# pH_Sensor_Unit.net
KiCad netlist of a schematic drawn in Altium Designer
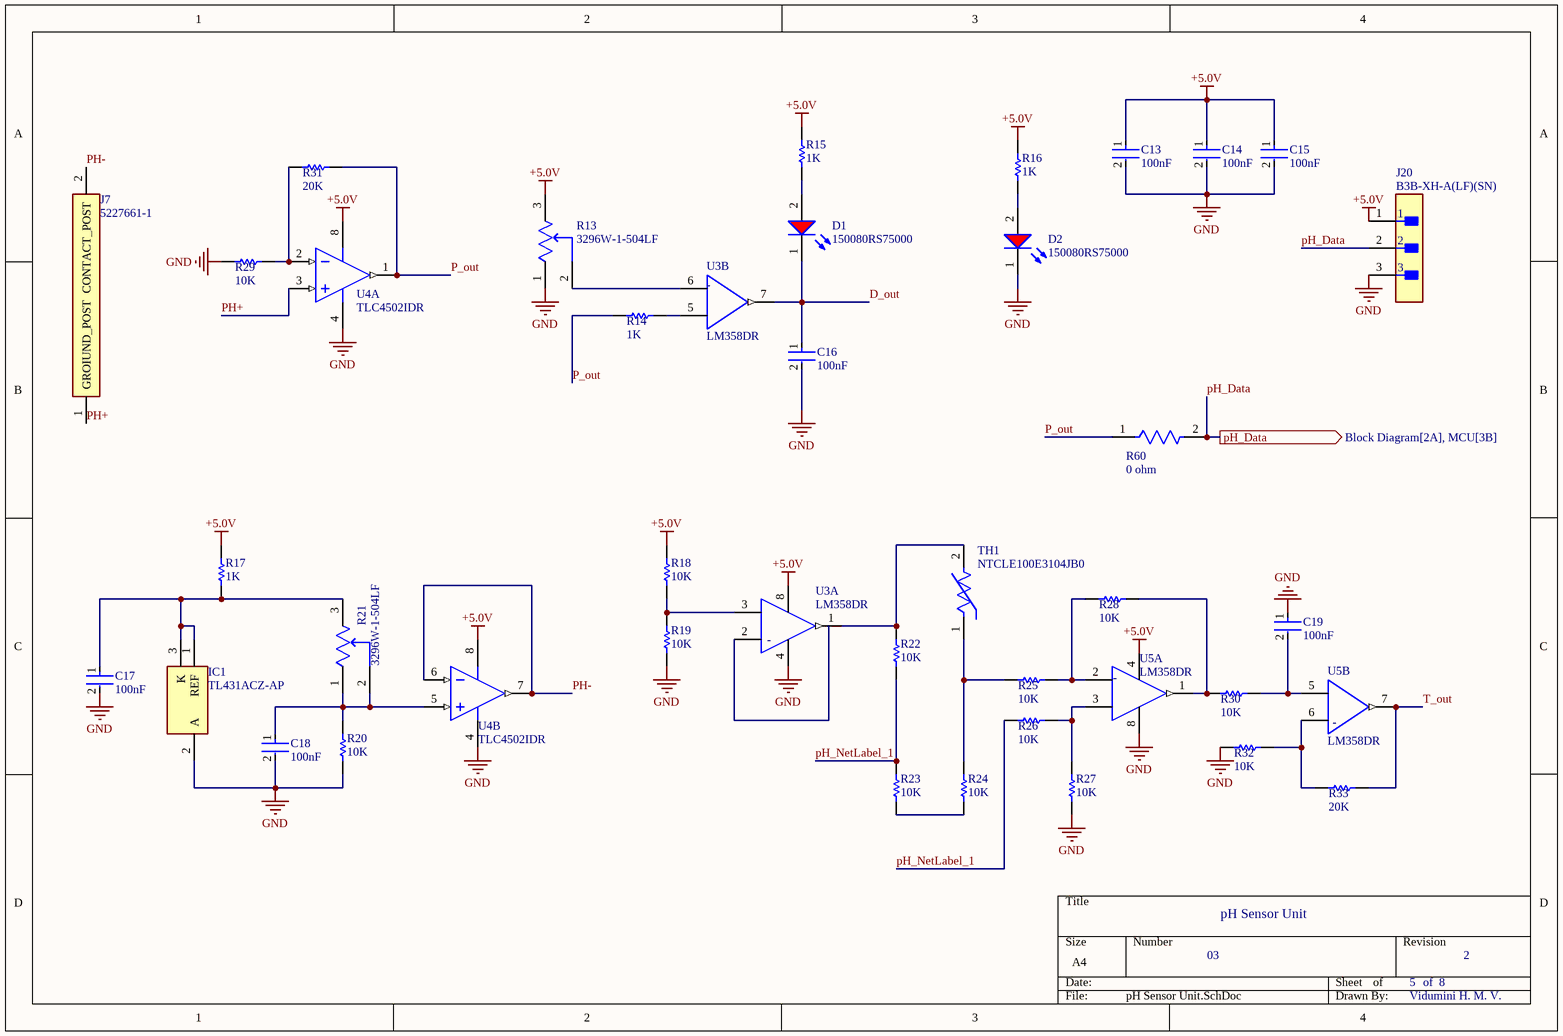
[diagram p0: pH Sensor Unit.SchDoc]

(export (version "E")
  (design (tool "Eeschema 10.0.6"))
  (components
    (comp (ref "C13")
      (value "100nF")
      (footprint "FP-1206-L_3_2_0_2-W_1_6_0-IPC_C")
      (description "General Purpose Ceramic Capacitor, 1206, 100nF, 5%, X7R, 15%, 100V")
      (fields (field (name "TOLERANCE") "5%") (field (name "VOLTAGE") "100V"))
      (libsource (lib "Altium Content Vault") (part "b4654b650e69147ec39a6b967a45e02"))
    )
    (comp (ref "C14")
      (value "100nF")
      (footprint "FP-1206-L_3_2_0_2-W_1_6_0-IPC_C")
      (description "General Purpose Ceramic Capacitor, 1206, 100nF, 5%, X7R, 15%, 100V")
      (fields (field (name "TOLERANCE") "5%") (field (name "VOLTAGE") "100V"))
      (libsource (lib "Altium Content Vault") (part "b4654b650e69147ec39a6b967a45e02"))
    )
    (comp (ref "C15")
      (value "100nF")
      (footprint "FP-1206-L_3_2_0_2-W_1_6_0-IPC_C")
      (description "General Purpose Ceramic Capacitor, 1206, 100nF, 5%, X7R, 15%, 100V")
      (fields (field (name "TOLERANCE") "5%") (field (name "VOLTAGE") "100V"))
      (libsource (lib "Altium Content Vault") (part "b4654b650e69147ec39a6b967a45e02"))
    )
    (comp (ref "C16")
      (value "100nF")
      (footprint "FP-1206-L_3_2_0_2-W_1_6_0-IPC_C")
      (description "General Purpose Ceramic Capacitor, 1206, 100nF, 5%, X7R, 15%, 100V")
      (fields (field (name "TOLERANCE") "5%") (field (name "VOLTAGE") "100V"))
      (libsource (lib "Altium Content Vault") (part "b4654b650e69147ec39a6b967a45e02"))
    )
    (comp (ref "C17")
      (value "100nF")
      (footprint "FP-1206-L_3_2_0_2-W_1_6_0-IPC_C")
      (description "General Purpose Ceramic Capacitor, 1206, 100nF, 5%, X7R, 15%, 100V")
      (fields (field (name "TOLERANCE") "5%") (field (name "VOLTAGE") "100V"))
      (libsource (lib "Altium Content Vault") (part "b4654b650e69147ec39a6b967a45e02"))
    )
    (comp (ref "C18")
      (value "100nF")
      (footprint "FP-1206-L_3_2_0_2-W_1_6_0-IPC_C")
      (description "General Purpose Ceramic Capacitor, 1206, 100nF, 5%, X7R, 15%, 100V")
      (fields (field (name "TOLERANCE") "5%") (field (name "VOLTAGE") "100V"))
      (libsource (lib "Altium Content Vault") (part "b4654b650e69147ec39a6b967a45e02"))
    )
    (comp (ref "C19")
      (value "100nF")
      (footprint "FP-1206-L_3_2_0_2-W_1_6_0-IPC_C")
      (description "General Purpose Ceramic Capacitor, 1206, 100nF, 5%, X7R, 15%, 100V")
      (fields (field (name "TOLERANCE") "5%") (field (name "VOLTAGE") "100V"))
      (libsource (lib "Altium Content Vault") (part "b4654b650e69147ec39a6b967a45e02"))
    )
    (comp (ref "D1")
      (value "150080RS75000")
      (footprint "WL-SMCW_0805_150080xx75000")
      (libsource (lib "Altium Content Vault") (part "LED_Red_2A-1K"))
    )
    (comp (ref "D2")
      (value "150080RS75000")
      (footprint "WL-SMCW_0805_150080xx75000")
      (libsource (lib "Altium Content Vault") (part "LED_Red_2A-1K"))
    )
    (comp (ref "IC1")
      (value "TL431ACZ-AP")
      (footprint "SamacSys:TO-92_BULK")
      (description "Integrated Circuit")
      (fields (field (name "MOUSER PART NUMBER") "511-TL431ACZ-AP"))
      (libsource (lib "*") (part "TL431ACZ-AP"))
    )
    (comp (ref "J7")
      (value "5227661-1")
      (footprint "SamacSys:5227161-1")
      (description "Connector")
      (fields (field (name "MOUSER PART NUMBER") "571-5227661-1"))
      (libsource (lib "*") (part "5227661-1"))
    )
    (comp (ref "J20")
      (value "B3B-XH-A(LF)(SN)")
      (footprint "FP-B3B-XH-A_LF_SN-MFG")
      (description "CONN HEADER VERT 3POS 2.5MM")
      (libsource (lib "Altium Content Vault") (part "0d3f023dd272f625e17a2be33dea85f"))
    )
    (comp (ref "R13")
      (value "3296W-1-504LF")
      (footprint "FP-3296W-MFG")
      (description "TRIMMER 500K OHM 0.5W PC PIN TOP")
      (fields
        (field (name "MANUFACTURER") "Bourns")
        (field (name "OCTOPART") "https://octopart.com/3296w-1-504lf-bourns-143884")
      )
      (libsource (lib "Altium Content Vault") (part "8d460c8a6f7ec10b1759d1b9c49aa93"))
    )
    (comp (ref "R14")
      (value "1K")
      (footprint "RESC3116X65X40ML10T20")
      (description "Chip Resistor, 10 KOhm, +/- 1%, 0.25 W, -55 to 155 degC, 1206 (3216 Metric), RoHS, Tape and Reel")
      (fields (field (name "TOLERANCE") "1%") (field (name "MANUFACTURER") "Yageo"))
      (libsource (lib "Altium Content Vault") (part "RES-2"))
    )
    (comp (ref "R15")
      (value "1K")
      (footprint "RESC3116X65X40ML10T20")
      (description "Chip Resistor, 10 KOhm, +/- 1%, 0.25 W, -55 to 155 degC, 1206 (3216 Metric), RoHS, Tape and Reel")
      (fields (field (name "TOLERANCE") "1%") (field (name "MANUFACTURER") "Yageo"))
      (libsource (lib "Altium Content Vault") (part "RES-2"))
    )
    (comp (ref "R16")
      (value "1K")
      (footprint "RESC3116X65X40ML10T20")
      (description "Chip Resistor, 10 KOhm, +/- 1%, 0.25 W, -55 to 155 degC, 1206 (3216 Metric), RoHS, Tape and Reel")
      (fields (field (name "TOLERANCE") "1%") (field (name "MANUFACTURER") "Yageo"))
      (libsource (lib "Altium Content Vault") (part "RES-2"))
    )
    (comp (ref "R17")
      (value "1K")
      (footprint "RESC3116X65X40ML10T20")
      (description "Chip Resistor, 10 KOhm, +/- 1%, 0.25 W, -55 to 155 degC, 1206 (3216 Metric), RoHS, Tape and Reel")
      (fields (field (name "TOLERANCE") "1%") (field (name "MANUFACTURER") "Yageo"))
      (libsource (lib "Altium Content Vault") (part "RES-2"))
    )
    (comp (ref "R18")
      (value "10K")
      (footprint "RESC3116X65X40ML10T20")
      (description "Chip Resistor, 10 KOhm, +/- 1%, 0.25 W, -55 to 155 degC, 1206 (3216 Metric), RoHS, Tape and Reel")
      (fields (field (name "TOLERANCE") "1%") (field (name "MANUFACTURER") "Yageo"))
      (libsource (lib "Altium Content Vault") (part "RES-2"))
    )
    (comp (ref "R19")
      (value "10K")
      (footprint "RESC3116X65X40ML10T20")
      (description "Chip Resistor, 10 KOhm, +/- 1%, 0.25 W, -55 to 155 degC, 1206 (3216 Metric), RoHS, Tape and Reel")
      (fields (field (name "TOLERANCE") "1%") (field (name "MANUFACTURER") "Yageo"))
      (libsource (lib "Altium Content Vault") (part "RES-2"))
    )
    (comp (ref "R20")
      (value "10K")
      (footprint "RESC3116X65X40ML10T20")
      (description "Chip Resistor, 10 KOhm, +/- 1%, 0.25 W, -55 to 155 degC, 1206 (3216 Metric), RoHS, Tape and Reel")
      (fields (field (name "TOLERANCE") "1%") (field (name "MANUFACTURER") "Yageo"))
      (libsource (lib "Altium Content Vault") (part "RES-2"))
    )
    (comp (ref "R21")
      (value "3296W-1-504LF")
      (footprint "FP-3296W-MFG")
      (description "TRIMMER 500K OHM 0.5W PC PIN TOP")
      (fields
        (field (name "MANUFACTURER") "Bourns")
        (field (name "OCTOPART") "https://octopart.com/3296w-1-504lf-bourns-143884")
      )
      (libsource (lib "Altium Content Vault") (part "8d460c8a6f7ec10b1759d1b9c49aa93"))
    )
    (comp (ref "R22")
      (value "10K")
      (footprint "RESC3116X65X40ML10T20")
      (description "Chip Resistor, 10 KOhm, +/- 1%, 0.25 W, -55 to 155 degC, 1206 (3216 Metric), RoHS, Tape and Reel")
      (fields (field (name "TOLERANCE") "1%") (field (name "MANUFACTURER") "Yageo"))
      (libsource (lib "Altium Content Vault") (part "RES-2"))
    )
    (comp (ref "R23")
      (value "10K")
      (footprint "RESC3116X65X40ML10T20")
      (description "Chip Resistor, 10 KOhm, +/- 1%, 0.25 W, -55 to 155 degC, 1206 (3216 Metric), RoHS, Tape and Reel")
      (fields (field (name "TOLERANCE") "1%") (field (name "MANUFACTURER") "Yageo"))
      (libsource (lib "Altium Content Vault") (part "RES-2"))
    )
    (comp (ref "R24")
      (value "10K")
      (footprint "RESC3116X65X40ML10T20")
      (description "Chip Resistor, 10 KOhm, +/- 1%, 0.25 W, -55 to 155 degC, 1206 (3216 Metric), RoHS, Tape and Reel")
      (fields (field (name "TOLERANCE") "1%") (field (name "MANUFACTURER") "Yageo"))
      (libsource (lib "Altium Content Vault") (part "RES-2"))
    )
    (comp (ref "R25")
      (value "10K")
      (footprint "RESC3116X65X40ML10T20")
      (description "Chip Resistor, 10 KOhm, +/- 1%, 0.25 W, -55 to 155 degC, 1206 (3216 Metric), RoHS, Tape and Reel")
      (fields (field (name "TOLERANCE") "1%") (field (name "MANUFACTURER") "Yageo"))
      (libsource (lib "Altium Content Vault") (part "RES-2"))
    )
    (comp (ref "R26")
      (value "10K")
      (footprint "RESC3116X65X40ML10T20")
      (description "Chip Resistor, 10 KOhm, +/- 1%, 0.25 W, -55 to 155 degC, 1206 (3216 Metric), RoHS, Tape and Reel")
      (fields (field (name "TOLERANCE") "1%") (field (name "MANUFACTURER") "Yageo"))
      (libsource (lib "Altium Content Vault") (part "RES-2"))
    )
    (comp (ref "R27")
      (value "10K")
      (footprint "RESC3116X65X40ML10T20")
      (description "Chip Resistor, 10 KOhm, +/- 1%, 0.25 W, -55 to 155 degC, 1206 (3216 Metric), RoHS, Tape and Reel")
      (fields (field (name "TOLERANCE") "1%") (field (name "MANUFACTURER") "Yageo"))
      (libsource (lib "Altium Content Vault") (part "RES-2"))
    )
    (comp (ref "R28")
      (value "10K")
      (footprint "RESC3116X65X40ML10T20")
      (description "Chip Resistor, 10 KOhm, +/- 1%, 0.25 W, -55 to 155 degC, 1206 (3216 Metric), RoHS, Tape and Reel")
      (fields (field (name "TOLERANCE") "1%") (field (name "MANUFACTURER") "Yageo"))
      (libsource (lib "Altium Content Vault") (part "RES-2"))
    )
    (comp (ref "R29")
      (value "10K")
      (footprint "RESC3116X65X40ML10T20")
      (description "Chip Resistor, 10 KOhm, +/- 1%, 0.25 W, -55 to 155 degC, 1206 (3216 Metric), RoHS, Tape and Reel")
      (fields (field (name "TOLERANCE") "1%") (field (name "MANUFACTURER") "Yageo"))
      (libsource (lib "Altium Content Vault") (part "RES-2"))
    )
    (comp (ref "R30")
      (value "10K")
      (footprint "RESC3116X65X40ML10T20")
      (description "Chip Resistor, 10 KOhm, +/- 1%, 0.25 W, -55 to 155 degC, 1206 (3216 Metric), RoHS, Tape and Reel")
      (fields (field (name "TOLERANCE") "1%") (field (name "MANUFACTURER") "Yageo"))
      (libsource (lib "Altium Content Vault") (part "RES-2"))
    )
    (comp (ref "R31")
      (value "20K")
      (footprint "RESC3116X65X40ML10T20")
      (description "Chip Resistor, 10 KOhm, +/- 1%, 0.25 W, -55 to 155 degC, 1206 (3216 Metric), RoHS, Tape and Reel")
      (fields (field (name "TOLERANCE") "1%") (field (name "MANUFACTURER") "Yageo"))
      (libsource (lib "Altium Content Vault") (part "RES-2"))
    )
    (comp (ref "R32")
      (value "10K")
      (footprint "RESC3116X65X40ML10T20")
      (description "Chip Resistor, 10 KOhm, +/- 1%, 0.25 W, -55 to 155 degC, 1206 (3216 Metric), RoHS, Tape and Reel")
      (fields (field (name "TOLERANCE") "1%") (field (name "MANUFACTURER") "Yageo"))
      (libsource (lib "Altium Content Vault") (part "RES-2"))
    )
    (comp (ref "R33")
      (value "20K")
      (footprint "RESC3116X65X40ML10T20")
      (description "Chip Resistor, 10 KOhm, +/- 1%, 0.25 W, -55 to 155 degC, 1206 (3216 Metric), RoHS, Tape and Reel")
      (fields (field (name "TOLERANCE") "1%") (field (name "MANUFACTURER") "Yageo"))
      (libsource (lib "Altium Content Vault") (part "RES-2"))
    )
    (comp (ref "R60")
      (value "0 ohm")
      (footprint "FP-AF0603-IPC_B")
      (description "Anti-Sulfurated Chip Resistors Automotive Grade 1.5kΩ 1% 100ppm/°C 0603")
      (fields (field (name "TOLERANCE") "1%"))
      (libsource (lib "Altium Content Vault") (part "1029c3af85768c4190bb7ad29bc67b5"))
    )
    (comp (ref "TH1")
      (value "NTCLE100E3104JB0")
      (footprint "FP-NTCLE100E3104JB0-MFG")
      (description "NTC THERMISTOR 100K OHM 5% BEAD")
      (fields (field (name "TOLERANCE") "5%"))
      (libsource (lib "Altium Content Vault") (part "3b148a6ebabc5fb4d708a66c052d352"))
    )
    (comp (ref "U3")
      (value "LM358DR")
      (footprint "FP-D0008A-MFG")
      (description "IC OPAMP GP 2 CIRCUIT 8SOIC")
      (libsource (lib "Altium Content Vault") (part "0afdfe5f461d2cdd85604ff8654be97"))
    )
    (comp (ref "U4")
      (value "TLC4502IDR")
      (footprint "D0008A_L")
      (fields (field (name "MANUFACTURER") "Texas Instruments"))
      (libsource (lib "Altium Content Vault") (part "TI-TLV_C2XX2_TLC4502-8"))
    )
    (comp (ref "U5")
      (value "LM358DR")
      (footprint "FP-D0008A-MFG")
      (description "IC OPAMP GP 2 CIRCUIT 8SOIC")
      (libsource (lib "Altium Content Vault") (part "0afdfe5f461d2cdd85604ff8654be97"))
    )
  )
  (nets
    (net (code "1") (name "+5.0V") (class "Default")
      (node (ref "C13") (pin "1") (pinfunction "1_1") (pintype "passive"))
      (node (ref "C14") (pin "1") (pinfunction "1_1") (pintype "passive"))
      (node (ref "C15") (pin "1") (pinfunction "1_1") (pintype "passive"))
      (node (ref "J20") (pin "1") (pinfunction "1_1") (pintype "passive"))
      (node (ref "R13") (pin "3") (pinfunction "CW_3") (pintype "passive"))
      (node (ref "R15") (pin "2") (pinfunction "2_2") (pintype "passive"))
      (node (ref "R16") (pin "2") (pinfunction "2_2") (pintype "passive"))
      (node (ref "R17") (pin "2") (pinfunction "2_2") (pintype "passive"))
      (node (ref "R18") (pin "2") (pinfunction "2_2") (pintype "passive"))
      (node (ref "U3") (pin "8") (pinfunction "V+_8") (pintype "power_in"))
      (node (ref "U4") (pin "8") (pinfunction "VDD+_8") (pintype "power_in"))
      (node (ref "U5") (pin "4") (pinfunction "V-_4") (pintype "power_in"))
    )
    (net (code "2") (name "/D_out") (class "Default")
      (node (ref "C16") (pin "1") (pinfunction "1_1") (pintype "passive"))
      (node (ref "D1") (pin "1") (pinfunction "K_1") (pintype "passive"))
      (node (ref "U3") (pin "7") (pinfunction "2OUT_7") (pintype "output"))
    )
    (net (code "3") (name "/PH+") (class "Default")
      (node (ref "J7") (pin "1") (pinfunction "GROIUND_POST_1") (pintype "passive"))
      (node (ref "U4") (pin "3") (pinfunction "IN1+_3") (pintype "input"))
    )
    (net (code "4") (name "/PH-") (class "Default")
      (node (ref "J7") (pin "2") (pinfunction "CONTACT_POST_2") (pintype "passive"))
      (node (ref "U4") (pin "6") (pinfunction "IN2-_6") (pintype "input"))
      (node (ref "U4") (pin "7") (pinfunction "OUT2_7") (pintype "output"))
    )
    (net (code "5") (name "/P_out") (class "Default")
      (node (ref "R14") (pin "2") (pinfunction "2_2") (pintype "passive"))
      (node (ref "R31") (pin "2") (pinfunction "2_2") (pintype "passive"))
      (node (ref "R60") (pin "1") (pinfunction "1_1") (pintype "passive"))
      (node (ref "U4") (pin "1") (pinfunction "OUT1_1") (pintype "output"))
    )
    (net (code "6") (name "/T_out") (class "Default")
      (node (ref "R33") (pin "2") (pinfunction "2_2") (pintype "passive"))
      (node (ref "U5") (pin "7") (pinfunction "2OUT_7") (pintype "output"))
    )
    (net (code "7") (name "/pH_Data") (class "Default")
      (node (ref "J20") (pin "2") (pinfunction "2_2") (pintype "passive"))
      (node (ref "R60") (pin "2") (pinfunction "2_2") (pintype "passive"))
    )
    (net (code "8") (name "/pH_NetLabel_1") (class "Default")
      (node (ref "R22") (pin "1") (pinfunction "1_1") (pintype "passive"))
      (node (ref "R23") (pin "2") (pinfunction "2_2") (pintype "passive"))
      (node (ref "R26") (pin "1") (pinfunction "1_1") (pintype "passive"))
    )
    (net (code "9") (name "GND") (class "Default")
      (node (ref "C13") (pin "2") (pinfunction "2_2") (pintype "passive"))
      (node (ref "C14") (pin "2") (pinfunction "2_2") (pintype "passive"))
      (node (ref "C15") (pin "2") (pinfunction "2_2") (pintype "passive"))
      (node (ref "C16") (pin "2") (pinfunction "2_2") (pintype "passive"))
      (node (ref "C17") (pin "2") (pinfunction "2_2") (pintype "passive"))
      (node (ref "C18") (pin "2") (pinfunction "2_2") (pintype "passive"))
      (node (ref "C19") (pin "1") (pinfunction "1_1") (pintype "passive"))
      (node (ref "D2") (pin "1") (pinfunction "K_1") (pintype "passive"))
      (node (ref "IC1") (pin "2") (pinfunction "A_2") (pintype "passive"))
      (node (ref "J20") (pin "3") (pinfunction "3_3") (pintype "passive"))
      (node (ref "R13") (pin "1") (pinfunction "CCW_1") (pintype "passive"))
      (node (ref "R19") (pin "1") (pinfunction "1_1") (pintype "passive"))
      (node (ref "R20") (pin "1") (pinfunction "1_1") (pintype "passive"))
      (node (ref "R27") (pin "1") (pinfunction "1_1") (pintype "passive"))
      (node (ref "R29") (pin "1") (pinfunction "1_1") (pintype "passive"))
      (node (ref "R32") (pin "1") (pinfunction "1_1") (pintype "passive"))
      (node (ref "U3") (pin "4") (pinfunction "V-_4") (pintype "power_in"))
      (node (ref "U4") (pin "4") (pinfunction "VDD-/GND_4") (pintype "power_in"))
      (node (ref "U5") (pin "8") (pinfunction "V+_8") (pintype "power_in"))
    )
    (net (code "10") (name "Net-(D1-A)") (class "Default")
      (node (ref "D1") (pin "2") (pinfunction "A_2") (pintype "passive"))
      (node (ref "R15") (pin "1") (pinfunction "1_1") (pintype "passive"))
    )
    (net (code "11") (name "Net-(D2-A)") (class "Default")
      (node (ref "D2") (pin "2") (pinfunction "A_2") (pintype "passive"))
      (node (ref "R16") (pin "1") (pinfunction "1_1") (pintype "passive"))
    )
    (net (code "12") (name "Net-(IC1-K)") (class "Default")
      (node (ref "C17") (pin "1") (pinfunction "1_1") (pintype "passive"))
      (node (ref "IC1") (pin "1") (pinfunction "REF_1") (pintype "passive"))
      (node (ref "IC1") (pin "3") (pinfunction "K_3") (pintype "passive"))
      (node (ref "R17") (pin "1") (pinfunction "1_1") (pintype "passive"))
      (node (ref "R21") (pin "3") (pinfunction "CW_3") (pintype "passive"))
    )
    (net (code "13") (name "Net-(R13-WIPER)") (class "Default")
      (node (ref "R13") (pin "2") (pinfunction "WIPER_2") (pintype "passive"))
      (node (ref "U3") (pin "6") (pinfunction "IN2-_6") (pintype "tri_state"))
    )
    (net (code "14") (name "Net-(R21-CCW)") (class "Default")
      (node (ref "C18") (pin "1") (pinfunction "1_1") (pintype "passive"))
      (node (ref "R20") (pin "2") (pinfunction "2_2") (pintype "passive"))
      (node (ref "R21") (pin "1") (pinfunction "CCW_1") (pintype "passive"))
      (node (ref "R21") (pin "2") (pinfunction "WIPER_2") (pintype "passive"))
      (node (ref "U4") (pin "5") (pinfunction "IN2+_5") (pintype "input"))
    )
    (net (code "15") (name "Net-(R23-Pad1)") (class "Default")
      (node (ref "R23") (pin "1") (pinfunction "1_1") (pintype "passive"))
      (node (ref "R24") (pin "1") (pinfunction "1_1") (pintype "passive"))
    )
    (net (code "16") (name "Net-(R24-Pad2)") (class "Default")
      (node (ref "R24") (pin "2") (pinfunction "2_2") (pintype "passive"))
      (node (ref "R25") (pin "1") (pinfunction "1_1") (pintype "passive"))
      (node (ref "TH1") (pin "1") (pinfunction "1_1") (pintype "passive"))
    )
    (net (code "17") (name "Net-(U3A-1OUT)") (class "Default")
      (node (ref "R22") (pin "2") (pinfunction "2_2") (pintype "passive"))
      (node (ref "TH1") (pin "2") (pinfunction "2_2") (pintype "passive"))
      (node (ref "U3") (pin "1") (pinfunction "1OUT_1") (pintype "output"))
    )
    (net (code "18") (name "Net-(U3A-IN1+)") (class "Default")
      (node (ref "R18") (pin "1") (pinfunction "1_1") (pintype "passive"))
      (node (ref "R19") (pin "2") (pinfunction "2_2") (pintype "passive"))
      (node (ref "U3") (pin "3") (pinfunction "IN1+_3") (pintype "tri_state"))
    )
    (net (code "19") (name "Net-(U3B-IN2+)") (class "Default")
      (node (ref "R14") (pin "1") (pinfunction "1_1") (pintype "passive"))
      (node (ref "U3") (pin "5") (pinfunction "IN2+_5") (pintype "tri_state"))
    )
    (net (code "20") (name "Net-(U4A-IN1-)") (class "Default")
      (node (ref "R29") (pin "2") (pinfunction "2_2") (pintype "passive"))
      (node (ref "R31") (pin "1") (pinfunction "1_1") (pintype "passive"))
      (node (ref "U4") (pin "2") (pinfunction "IN1-_2") (pintype "input"))
    )
    (net (code "21") (name "Net-(U5A-1OUT)") (class "Default")
      (node (ref "R28") (pin "2") (pinfunction "2_2") (pintype "passive"))
      (node (ref "R30") (pin "1") (pinfunction "1_1") (pintype "passive"))
      (node (ref "U5") (pin "1") (pinfunction "1OUT_1") (pintype "output"))
    )
    (net (code "22") (name "Net-(U5A-IN1+)") (class "Default")
      (node (ref "R26") (pin "2") (pinfunction "2_2") (pintype "passive"))
      (node (ref "R27") (pin "2") (pinfunction "2_2") (pintype "passive"))
      (node (ref "U5") (pin "3") (pinfunction "IN1+_3") (pintype "tri_state"))
    )
    (net (code "23") (name "Net-(U5A-IN1-)") (class "Default")
      (node (ref "R25") (pin "2") (pinfunction "2_2") (pintype "passive"))
      (node (ref "R28") (pin "1") (pinfunction "1_1") (pintype "passive"))
      (node (ref "U5") (pin "2") (pinfunction "IN1-_2") (pintype "tri_state"))
    )
    (net (code "24") (name "Net-(U5B-IN2+)") (class "Default")
      (node (ref "C19") (pin "2") (pinfunction "2_2") (pintype "passive"))
      (node (ref "R30") (pin "2") (pinfunction "2_2") (pintype "passive"))
      (node (ref "U5") (pin "5") (pinfunction "IN2+_5") (pintype "tri_state"))
    )
    (net (code "25") (name "Net-(U5B-IN2-)") (class "Default")
      (node (ref "R32") (pin "2") (pinfunction "2_2") (pintype "passive"))
      (node (ref "R33") (pin "1") (pinfunction "1_1") (pintype "passive"))
      (node (ref "U5") (pin "6") (pinfunction "IN2-_6") (pintype "tri_state"))
    )
    (net (code "26") (name "unconnected-(U3A-IN1--Pad2)") (class "Default")
      (node (ref "U3") (pin "2") (pinfunction "IN1-_2") (pintype "tri_state"))
    )
  )
)
